# Thermostat_Thorlabs.net
KiCad netlist of a schematic drawn in Altium Designer
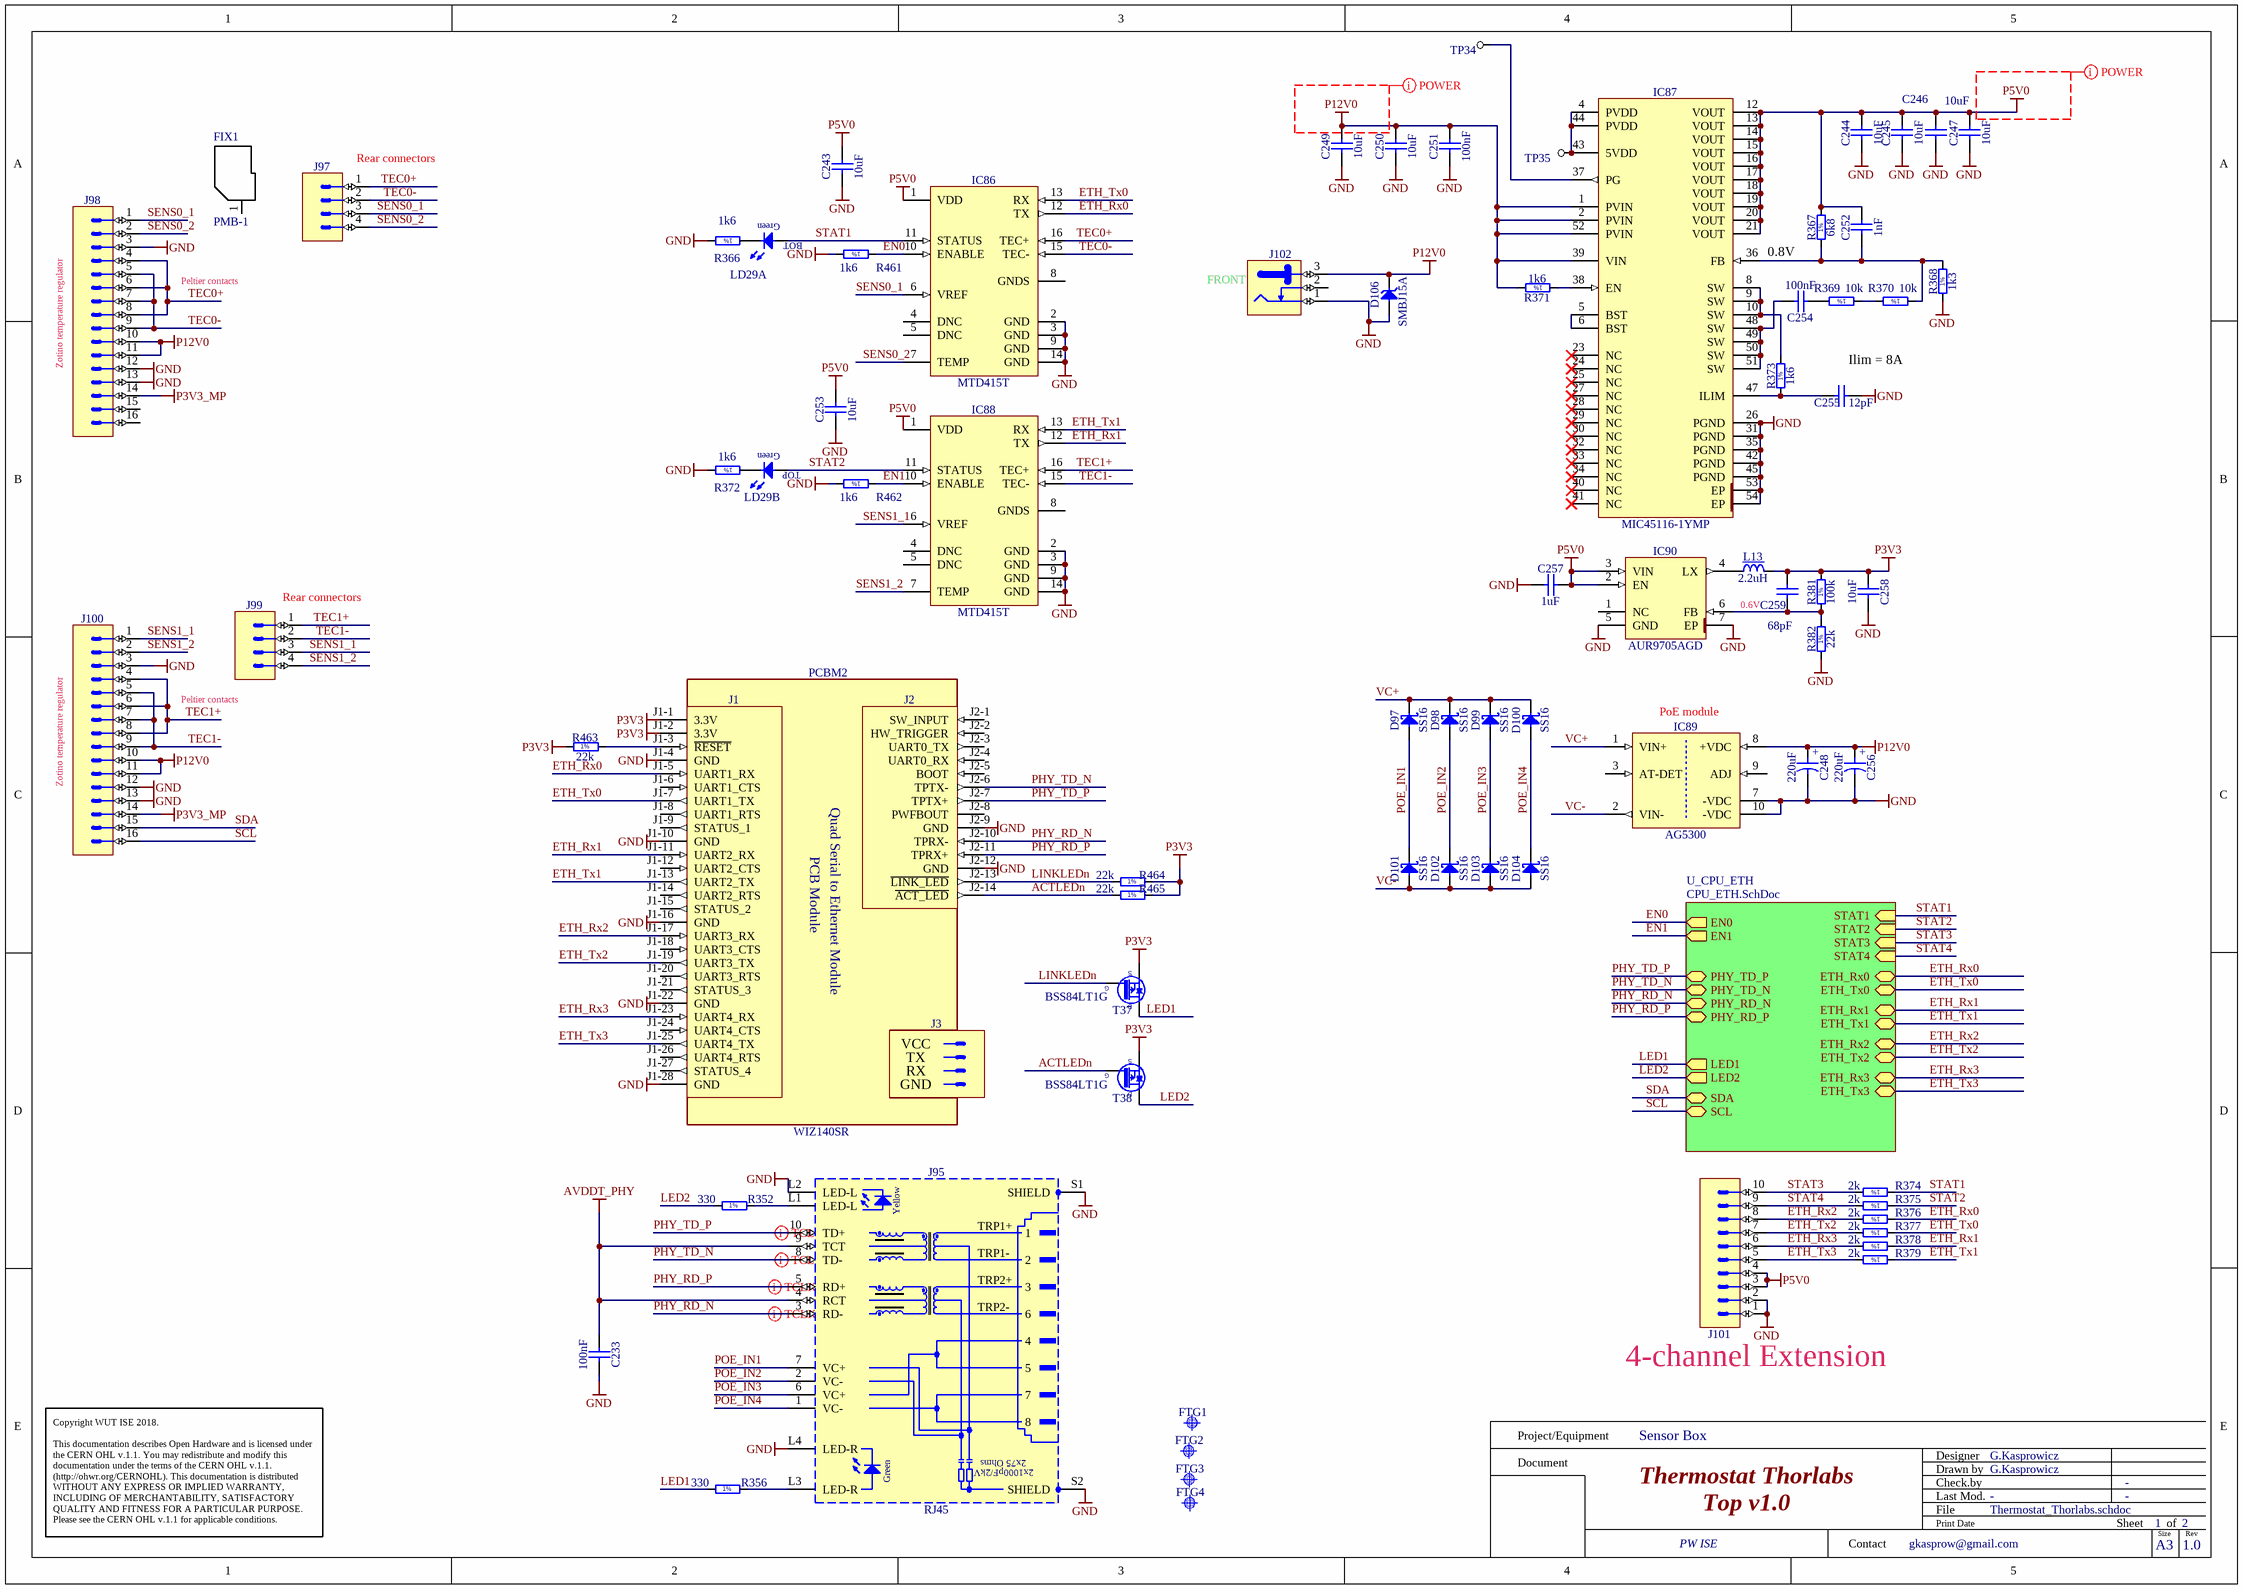
[diagram p0: Thermostat_Thorlabs.schdoc]

(export (version "E")
  (design (tool "Eeschema 10.0.6"))
  (components
    (comp (ref "C233")
      (value "100nF")
      (footprint "CAPC1005X55N")
      (description "Non-polarised capacitor")
      (fields (field (name "PART NUMBER") "CC0402_100NF_16V_10%_X5R") (field (name "VOLTAGE") "16V"))
      (libsource (lib "Capacitors") (part "Capacitor - non polarized"))
    )
    (comp (ref "C243")
      (value "10uF")
      (footprint "CAPC2012X135N")
      (description "Non-polarised capacitor")
      (fields (field (name "PART NUMBER") "CC0805_10UF_16V_10%_X5R") (field (name "VOLTAGE") "16V"))
      (libsource (lib "Capacitors") (part "Capacitor - non polarized"))
    )
    (comp (ref "C244")
      (value "10uF")
      (footprint "CAPC2012X135N")
      (description "Non-polarised capacitor")
      (fields (field (name "PART NUMBER") "CC0805_10UF_16V_10%_X5R") (field (name "VOLTAGE") "16V"))
      (libsource (lib "Capacitors") (part "Capacitor - non polarized"))
    )
    (comp (ref "C245")
      (value "10uF")
      (footprint "CAPC2012X135N")
      (description "Non-polarised capacitor")
      (fields (field (name "PART NUMBER") "CC0805_10UF_16V_10%_X5R") (field (name "VOLTAGE") "16V"))
      (libsource (lib "Capacitors") (part "Capacitor - non polarized"))
    )
    (comp (ref "C246")
      (value "10uF")
      (footprint "CAPC2012X135N")
      (description "Non-polarised capacitor")
      (fields (field (name "PART NUMBER") "CC0805_10UF_16V_10%_X5R") (field (name "VOLTAGE") "16V"))
      (libsource (lib "Capacitors") (part "Capacitor - non polarized"))
    )
    (comp (ref "C247")
      (value "10uF")
      (footprint "CAPC2012X135N")
      (description "Non-polarised capacitor")
      (fields (field (name "PART NUMBER") "CC0805_10UF_16V_10%_X5R") (field (name "VOLTAGE") "16V"))
      (libsource (lib "Capacitors") (part "Capacitor - non polarized"))
    )
    (comp (ref "C248")
      (value "220uF")
      (footprint "CAPMP7343X430N")
      (description "Polarised capacitor")
      (fields (field (name "PART NUMBER") "CTE7343-43_220UF_16V_10%") (field (name "VOLTAGE") "16V"))
      (libsource (lib "Capacitors") (part "Capacitor - polarized"))
    )
    (comp (ref "C249")
      (value "10uF")
      (footprint "CAPC2012X135N")
      (description "Non-polarised capacitor")
      (fields (field (name "PART NUMBER") "CC0805_10UF_16V_10%_X5R") (field (name "VOLTAGE") "16V"))
      (libsource (lib "Capacitors") (part "Capacitor - non polarized"))
    )
    (comp (ref "C250")
      (value "10uF")
      (footprint "CAPC2012X135N")
      (description "Non-polarised capacitor")
      (fields (field (name "PART NUMBER") "CC0805_10UF_16V_10%_X5R") (field (name "VOLTAGE") "16V"))
      (libsource (lib "Capacitors") (part "Capacitor - non polarized"))
    )
    (comp (ref "C251")
      (value "100nF")
      (footprint "CAPC1005X55N")
      (description "Non-polarised capacitor")
      (fields (field (name "PART NUMBER") "CC0402_100NF_16V_10%_X5R") (field (name "VOLTAGE") "16V"))
      (libsource (lib "Capacitors") (part "Capacitor - non polarized"))
    )
    (comp (ref "C252")
      (value "1nF")
      (footprint "CAPC1608X87N")
      (description "Non-polarised capacitor")
      (fields (field (name "PART NUMBER") "CC0603_1NF_100V_10%_X7R") (field (name "VOLTAGE") "100V"))
      (libsource (lib "Capacitors") (part "Capacitor - non polarized"))
    )
    (comp (ref "C253")
      (value "10uF")
      (footprint "CAPC2012X135N")
      (description "Non-polarised capacitor")
      (fields (field (name "PART NUMBER") "CC0805_10UF_16V_10%_X5R") (field (name "VOLTAGE") "16V"))
      (libsource (lib "Capacitors") (part "Capacitor - non polarized"))
    )
    (comp (ref "C254")
      (value "100nF")
      (footprint "CAPC1005X55N")
      (description "Non-polarised capacitor")
      (fields (field (name "PART NUMBER") "CC0402_100NF_16V_10%_X5R") (field (name "VOLTAGE") "16V"))
      (libsource (lib "Capacitors") (part "Capacitor - non polarized"))
    )
    (comp (ref "C255")
      (value "12pF")
      (footprint "CAPC1005X55N")
      (description "Non-polarised capacitor")
      (fields (field (name "PART NUMBER") "CC0402_12PF_50V_5%_C0G") (field (name "VOLTAGE") "50V"))
      (libsource (lib "Capacitors") (part "Capacitor - non polarized"))
    )
    (comp (ref "C256")
      (value "220uF")
      (footprint "CAPMP7343X430N")
      (description "Polarised capacitor")
      (fields (field (name "PART NUMBER") "CTE7343-43_220UF_16V_10%") (field (name "VOLTAGE") "16V"))
      (libsource (lib "Capacitors") (part "Capacitor - polarized"))
    )
    (comp (ref "C257")
      (value "1uF")
      (footprint "CAPC1005X55N")
      (description "Non-polarised capacitor")
      (fields (field (name "PART NUMBER") "CC0402_1UF_16V_10%_X5R") (field (name "VOLTAGE") "16V"))
      (libsource (lib "Capacitors") (part "Capacitor - non polarized"))
    )
    (comp (ref "C258")
      (value "10uF")
      (footprint "CAPC2012X135N")
      (description "Non-polarised capacitor")
      (fields (field (name "PART NUMBER") "CC0805_10UF_16V_10%_X5R") (field (name "VOLTAGE") "16V"))
      (libsource (lib "Capacitors") (part "Capacitor - non polarized"))
    )
    (comp (ref "C259")
      (value "68pF")
      (footprint "CAPC1608X87N")
      (description "Non-polarised capacitor")
      (fields (field (name "PART NUMBER") "CC0603_68PF_50V_5%_NP0") (field (name "VOLTAGE") "50V"))
      (libsource (lib "Capacitors") (part "Capacitor - non polarized"))
    )
    (comp (ref "D97")
      (value "SS16")
      (footprint "DIOM5127X229N")
      (description "Schottky Diode")
      (fields (field (name "VOLTAGE") "60V") (field (name "POWER") "1A"))
      (libsource (lib "ICs And Semiconductors") (part "Diode Schottky"))
    )
    (comp (ref "D98")
      (value "SS16")
      (footprint "DIOM5127X229N")
      (description "Schottky Diode")
      (fields (field (name "VOLTAGE") "60V") (field (name "POWER") "1A"))
      (libsource (lib "ICs And Semiconductors") (part "Diode Schottky"))
    )
    (comp (ref "D99")
      (value "SS16")
      (footprint "DIOM5127X229N")
      (description "Schottky Diode")
      (fields (field (name "VOLTAGE") "60V") (field (name "POWER") "1A"))
      (libsource (lib "ICs And Semiconductors") (part "Diode Schottky"))
    )
    (comp (ref "D100")
      (value "SS16")
      (footprint "DIOM5127X229N")
      (description "Schottky Diode")
      (fields (field (name "VOLTAGE") "60V") (field (name "POWER") "1A"))
      (libsource (lib "ICs And Semiconductors") (part "Diode Schottky"))
    )
    (comp (ref "D101")
      (value "SS16")
      (footprint "DIOM5127X229N")
      (description "Schottky Diode")
      (fields (field (name "VOLTAGE") "60V") (field (name "POWER") "1A"))
      (libsource (lib "ICs And Semiconductors") (part "Diode Schottky"))
    )
    (comp (ref "D102")
      (value "SS16")
      (footprint "DIOM5127X229N")
      (description "Schottky Diode")
      (fields (field (name "VOLTAGE") "60V") (field (name "POWER") "1A"))
      (libsource (lib "ICs And Semiconductors") (part "Diode Schottky"))
    )
    (comp (ref "D103")
      (value "SS16")
      (footprint "DIOM5127X229N")
      (description "Schottky Diode")
      (fields (field (name "VOLTAGE") "60V") (field (name "POWER") "1A"))
      (libsource (lib "ICs And Semiconductors") (part "Diode Schottky"))
    )
    (comp (ref "D104")
      (value "SS16")
      (footprint "DIOM5127X229N")
      (description "Schottky Diode")
      (fields (field (name "VOLTAGE") "60V") (field (name "POWER") "1A"))
      (libsource (lib "ICs And Semiconductors") (part "Diode Schottky"))
    )
    (comp (ref "D106")
      (value "SMBJ15A")
      (footprint "DIOM5336X265N")
      (description "Zener Diode")
      (fields (field (name "VOLTAGE") "15V") (field (name "POWER") "600W"))
      (libsource (lib "ICs And Semiconductors") (part "Diode Zener"))
    )
    (comp (ref "FIX1")
      (value "PMB-1")
      (footprint "PMB-1")
      (description "right angle PCB fixing")
      (libsource (lib "LIBRARY_SCH") (part "MECH_PCB_FIX_RA"))
    )
    (comp (ref "FTG1")
      (value "Use only in PCB")
      (footprint "FIDUCIAL_TOP_C100-200")
      (description "Fiducial Target")
      (fields (field (name "PART NUMBER") "FIDUCIAL_TARGET_C100-200"))
      (libsource (lib "Eletro-mechanical") (part "Fiducial Target"))
    )
    (comp (ref "FTG2")
      (value "Use only in PCB")
      (footprint "FIDUCIAL_TOP_S100-200")
      (description "Fiducial Target")
      (fields (field (name "PART NUMBER") "FIDUCIAL_TARGET_S100-200"))
      (libsource (lib "Eletro-mechanical") (part "Fiducial Target"))
    )
    (comp (ref "FTG3")
      (value "Use only in PCB")
      (footprint "FIDUCIAL_TOP_S200-400")
      (description "Fiducial Target")
      (fields (field (name "PART NUMBER") "FIDUCIAL_TARGET_S200-400"))
      (libsource (lib "Eletro-mechanical") (part "Fiducial Target"))
    )
    (comp (ref "FTG4")
      (value "Use only in PCB")
      (footprint "FIDUCIAL_TOP_S100-200")
      (description "Fiducial Target")
      (fields (field (name "PART NUMBER") "FIDUCIAL_TARGET_S100-200"))
      (libsource (lib "Eletro-mechanical") (part "Fiducial Target"))
    )
    (comp (ref "IC86")
      (value "MTD415T")
      (footprint "THORLABS_MTD415T")
      (description "Miniature Temperature Controller, ±1.5 A, Compatible with 10 kΩ Thermistor")
      (fields (field (name "MANUFACTURER") "THORLABS"))
      (libsource (lib "ICs And Semiconductors") (part "MTD415T"))
    )
    (comp (ref "IC87")
      (value "MIC45116-1YMP")
      (footprint "MICROCHIP_H3QFN88-52LD-PL-3")
      (description "0.8V to 85% PVIN (4.75-19V), 6A Synchronous Step-Down Regulator Module")
      (fields (field (name "MANUFACTURER") "MICROCHIP TECHNOLOGY"))
      (libsource (lib "ICs And Semiconductors") (part "MIC45116"))
    )
    (comp (ref "IC88")
      (value "MTD415T")
      (footprint "THORLABS_MTD415T")
      (description "Miniature Temperature Controller, ±1.5 A, Compatible with 10 kΩ Thermistor")
      (fields (field (name "MANUFACTURER") "THORLABS"))
      (libsource (lib "ICs And Semiconductors") (part "MTD415T"))
    )
    (comp (ref "IC89")
      (value "AG5300")
      (footprint "SILVERTEL_AG5300")
      (description "Power-over-Ethernet Plus (POE+) Module")
      (fields (field (name "MANUFACTURER") "SILVERTEL"))
      (libsource (lib "ICs And Semiconductors") (part "AG5300"))
    )
    (comp (ref "IC90")
      (value "AUR9705AGD")
      (footprint "SON65P200X200X80-7N-R65X145")
      (description "0V to 6V Input, 1A, 1.5MHz, Step-Down DC-DC Converter")
      (fields (field (name "MANUFACTURER") "DIODES INCORPORATED"))
      (libsource (lib "ICs And Semiconductors") (part "AUR9705AGD"))
    )
    (comp (ref "J95")
      (value "RJ45")
      (footprint "ABRACON_ARJM11C7-114-BA-EW2")
      (description "MagJack 10/100BaseT, PoE+, 1X1, OG/Y, -40 to 85*C, Tab Up, RoHS")
      (fields (field (name "PART NUMBER") "ARJM11C7-114-BA-EW2") (field (name "MANUFACTURER") "Abracon"))
      (libsource (lib "LIBRARY_SCH") (part "CON_ETH_POE_ARJM11C7"))
    )
    (comp (ref "J97")
      (value "~")
      (footprint "FCI_20020110-D041A01LF")
      (description "Connector 4 Male")
      (fields (field (name "PART NUMBER") "FCI_20020110-D041A01LF") (field (name "MANUFACTURER") "FCI"))
      (libsource (lib "Connectors") (part "Connector 4 Male"))
    )
    (comp (ref "J98")
      (value "Header 16")
      (footprint "3M_N2516-6002RB")
      (description "Connector 16 Male")
      (fields (field (name "PART NUMBER") "3M_N2516-6002RB") (field (name "MANUFACTURER") "3M"))
      (libsource (lib "Connectors") (part "Connector 16 Male"))
    )
    (comp (ref "J99")
      (value "~")
      (footprint "FCI_20020110-D041A01LF")
      (description "Connector 4 Male")
      (fields (field (name "PART NUMBER") "FCI_20020110-D041A01LF") (field (name "MANUFACTURER") "FCI"))
      (libsource (lib "Connectors") (part "Connector 4 Male"))
    )
    (comp (ref "J100")
      (value "Header 16")
      (footprint "3M_N2516-6002RB")
      (description "Connector 16 Male")
      (fields (field (name "PART NUMBER") "3M_N2516-6002RB") (field (name "MANUFACTURER") "3M"))
      (libsource (lib "Connectors") (part "Connector 16 Male"))
    )
    (comp (ref "J101")
      (value "Header 10")
      (footprint "3M_N2510-6002RB")
      (description "Connector 10 Male")
      (fields (field (name "PART NUMBER") "3M_N2510-6002RB") (field (name "MANUFACTURER") "3M"))
      (libsource (lib "Connectors") (part "Connector 10 Male"))
    )
    (comp (ref "J102")
      (value "Jack")
      (footprint "SWITCHCRAFT_L712RA")
      (description "24V /3. 5A, 2.1mm Diameter Pin, SMD DC Power Supply Connector With  Break Contact")
      (fields (field (name "PART NUMBER") "SWITCHCRAFT_712RA") (field (name "MANUFACTURER") "SWITCHCRAFT"))
      (libsource (lib "LIBRARY_SCH") (part "CON_DC_5A_THT_RA"))
    )
    (comp (ref "L13")
      (value "2.2uH")
      (footprint "IND_MURATA_LQH44PN_P0")
      (description "Inductor With Core")
      (fields
        (field (name "PART NUMBER") "IND_2.2UH_20%_MURATA_LQH44PN2R2MP0L")
        (field (name "POWER") "1.8A")
      )
      (libsource (lib "Inductors & Transformers") (part "Inductor With Magnetic core"))
    )
    (comp (ref "LD29")
      (value "Green/Green")
      (footprint "LED_DIALIGHT_571-0122F")
      (description "LED x2 Green 1C2A-BOT_3C4A-TOP")
      (fields (field (name "PART NUMBER") "LED_DIALIGHT_571-0122F") (field (name "MANUFACTURER") "DIALIGHT"))
      (libsource (lib "ICs And Semiconductors") (part "LED x2 Green 1C2A-BOT_3C4A-TOP"))
    )
    (comp (ref "PCBM2")
      (value "WIZ140SR")
      (footprint "PCBM_WIZNET_WIZ140SR_a")
      (description "Quad Serial to Ethernet Module Based on W5300 & Cortex-M3")
      (fields (field (name "PART NUMBER") "PCBM_WIZNET_WIZ140SR_a") (field (name "MANUFACTURER") "WIZNET"))
      (libsource (lib "ICs And Semiconductors") (part "PCBM_WIZNET_WIZ140SR_a"))
    )
    (comp (ref "R352")
      (value "330")
      (footprint "RESC1005X40N")
      (description "Resistor - 1%")
      (fields (field (name "PART NUMBER") "R0402_330R_1%_0.0625W_100PPM") (field (name "POWER") "0.0625W"))
      (libsource (lib "Resistors") (part "Resistor - 1%"))
    )
    (comp (ref "R356")
      (value "330")
      (footprint "RESC1005X40N")
      (description "Resistor - 1%")
      (fields (field (name "PART NUMBER") "R0402_330R_1%_0.0625W_100PPM") (field (name "POWER") "0.0625W"))
      (libsource (lib "Resistors") (part "Resistor - 1%"))
    )
    (comp (ref "R366")
      (value "1k6")
      (footprint "RESC1005X40N")
      (description "Resistor - 1%")
      (fields (field (name "PART NUMBER") "R0402_1K6_1%_0.0625W_100PPM") (field (name "POWER") "0.0625W"))
      (libsource (lib "Resistors") (part "Resistor - 1%"))
    )
    (comp (ref "R367")
      (value "6k8")
      (footprint "RESC1005X40N")
      (description "Resistor - 1%")
      (fields (field (name "PART NUMBER") "R0402_6K8_1%_0.0625W_100PPM") (field (name "POWER") "0.0625W"))
      (libsource (lib "Resistors") (part "Resistor - 1%"))
    )
    (comp (ref "R368")
      (value "1k3")
      (footprint "RESC1608X55N")
      (description "Resistor - 1%")
      (fields (field (name "PART NUMBER") "R0603_1K3_1%_0.1W_100PPM") (field (name "POWER") "0.1W"))
      (libsource (lib "Resistors") (part "Resistor - 1%"))
    )
    (comp (ref "R369")
      (value "10k")
      (footprint "RESC1005X40N")
      (description "Resistor - 1%")
      (fields (field (name "PART NUMBER") "R0402_10K_1%_0.0625W_100PPM") (field (name "POWER") "0.0625W"))
      (libsource (lib "Resistors") (part "Resistor - 1%"))
    )
    (comp (ref "R370")
      (value "10k")
      (footprint "RESC1005X40N")
      (description "Resistor - 1%")
      (fields (field (name "PART NUMBER") "R0402_10K_1%_0.0625W_100PPM") (field (name "POWER") "0.0625W"))
      (libsource (lib "Resistors") (part "Resistor - 1%"))
    )
    (comp (ref "R371")
      (value "1k6")
      (footprint "RESC1005X40N")
      (description "Resistor - 1%")
      (fields (field (name "PART NUMBER") "R0402_1K6_1%_0.0625W_100PPM") (field (name "POWER") "0.0625W"))
      (libsource (lib "Resistors") (part "Resistor - 1%"))
    )
    (comp (ref "R372")
      (value "1k6")
      (footprint "RESC1005X40N")
      (description "Resistor - 1%")
      (fields (field (name "PART NUMBER") "R0402_1K6_1%_0.0625W_100PPM") (field (name "POWER") "0.0625W"))
      (libsource (lib "Resistors") (part "Resistor - 1%"))
    )
    (comp (ref "R373")
      (value "1k6")
      (footprint "RESC1005X40N")
      (description "Resistor - 1%")
      (fields (field (name "PART NUMBER") "R0402_1K6_1%_0.0625W_100PPM") (field (name "POWER") "0.0625W"))
      (libsource (lib "Resistors") (part "Resistor - 1%"))
    )
    (comp (ref "R374")
      (value "2k")
      (footprint "RESC1005X40N")
      (description "Resistor - 1%")
      (fields (field (name "PART NUMBER") "R0402_2K_1%_0.0625W_100PPM") (field (name "POWER") "0.0625W"))
      (libsource (lib "Resistors") (part "Resistor - 1%"))
    )
    (comp (ref "R375")
      (value "2k")
      (footprint "RESC1005X40N")
      (description "Resistor - 1%")
      (fields (field (name "PART NUMBER") "R0402_2K_1%_0.0625W_100PPM") (field (name "POWER") "0.0625W"))
      (libsource (lib "Resistors") (part "Resistor - 1%"))
    )
    (comp (ref "R376")
      (value "2k")
      (footprint "RESC1005X40N")
      (description "Resistor - 1%")
      (fields (field (name "PART NUMBER") "R0402_2K_1%_0.0625W_100PPM") (field (name "POWER") "0.0625W"))
      (libsource (lib "Resistors") (part "Resistor - 1%"))
    )
    (comp (ref "R377")
      (value "2k")
      (footprint "RESC1005X40N")
      (description "Resistor - 1%")
      (fields (field (name "PART NUMBER") "R0402_2K_1%_0.0625W_100PPM") (field (name "POWER") "0.0625W"))
      (libsource (lib "Resistors") (part "Resistor - 1%"))
    )
    (comp (ref "R378")
      (value "2k")
      (footprint "RESC1005X40N")
      (description "Resistor - 1%")
      (fields (field (name "PART NUMBER") "R0402_2K_1%_0.0625W_100PPM") (field (name "POWER") "0.0625W"))
      (libsource (lib "Resistors") (part "Resistor - 1%"))
    )
    (comp (ref "R379")
      (value "2k")
      (footprint "RESC1005X40N")
      (description "Resistor - 1%")
      (fields (field (name "PART NUMBER") "R0402_2K_1%_0.0625W_100PPM") (field (name "POWER") "0.0625W"))
      (libsource (lib "Resistors") (part "Resistor - 1%"))
    )
    (comp (ref "R381")
      (value "100k")
      (footprint "RESC1005X40N")
      (description "Resistor - 1%")
      (fields (field (name "PART NUMBER") "R0402_100K_1%_0.0625W_100PPM") (field (name "POWER") "0.0625W"))
      (libsource (lib "Resistors") (part "Resistor - 1%"))
    )
    (comp (ref "R382")
      (value "22k")
      (footprint "RESC1005X40N")
      (description "Resistor - 1%")
      (fields (field (name "PART NUMBER") "R0402_22K_1%_0.0625W_100PPM") (field (name "POWER") "0.0625W"))
      (libsource (lib "Resistors") (part "Resistor - 1%"))
    )
    (comp (ref "R461")
      (value "1k6")
      (footprint "RESC1005X40N")
      (description "Resistor - 1%")
      (fields (field (name "PART NUMBER") "R0402_1K6_1%_0.0625W_100PPM") (field (name "POWER") "0.0625W"))
      (libsource (lib "Resistors") (part "Resistor - 1%"))
    )
    (comp (ref "R462")
      (value "1k6")
      (footprint "RESC1005X40N")
      (description "Resistor - 1%")
      (fields (field (name "PART NUMBER") "R0402_1K6_1%_0.0625W_100PPM") (field (name "POWER") "0.0625W"))
      (libsource (lib "Resistors") (part "Resistor - 1%"))
    )
    (comp (ref "R463")
      (value "22k")
      (footprint "RESC1005X40N")
      (description "Resistor - 1%")
      (fields (field (name "PART NUMBER") "R0402_22K_1%_0.0625W_100PPM") (field (name "POWER") "0.0625W"))
      (libsource (lib "Resistors") (part "Resistor - 1%"))
    )
    (comp (ref "R464")
      (value "22k")
      (footprint "RESC1005X40N")
      (description "Resistor - 1%")
      (fields (field (name "PART NUMBER") "R0402_22K_1%_0.0625W_100PPM") (field (name "POWER") "0.0625W"))
      (libsource (lib "Resistors") (part "Resistor - 1%"))
    )
    (comp (ref "R465")
      (value "22k")
      (footprint "RESC1005X40N")
      (description "Resistor - 1%")
      (fields (field (name "PART NUMBER") "R0402_22K_1%_0.0625W_100PPM") (field (name "POWER") "0.0625W"))
      (libsource (lib "Resistors") (part "Resistor - 1%"))
    )
    (comp (ref "T37")
      (value "BSS84LT1G")
      (footprint "SOT95P240X110-3N")
      (description "P-CHANNEL MOSFET WITH DIODE")
      (fields (field (name "MANUFACTURER") "ON SEMICONDUCTOR"))
      (libsource (lib "ICs And Semiconductors") (part "P-MOSFET-D 1G 2S 3D"))
    )
    (comp (ref "T38")
      (value "BSS84LT1G")
      (footprint "SOT95P240X110-3N")
      (description "P-CHANNEL MOSFET WITH DIODE")
      (fields (field (name "MANUFACTURER") "ON SEMICONDUCTOR"))
      (libsource (lib "ICs And Semiconductors") (part "P-MOSFET-D 1G 2S 3D"))
    )
    (comp (ref "TP34")
      (value "TP")
      (footprint "TP")
      (description "Testpoint")
      (libsource (lib "LIBRARY_SCH") (part "TP"))
    )
    (comp (ref "TP35")
      (value "TP")
      (footprint "TP")
      (description "Testpoint")
      (libsource (lib "LIBRARY_SCH") (part "TP"))
    )
  )
  (nets
    (net (code "1") (name "/ACTLEDn") (class "Default")
      (node (ref "PCBM2") (pin "J2-14") (pinfunction "~{ACT_LED}_J2-14") (pintype "output"))
      (node (ref "R465") (pin "1") (pinfunction "1_1") (pintype "passive"))
      (node (ref "T38") (pin "1") (pinfunction "G_1") (pintype "passive"))
    )
    (net (code "2") (name "/EN0") (class "Default")
      (node (ref "IC86") (pin "10") (pinfunction "ENABLE_10") (pintype "input"))
      (node (ref "R461") (pin "1") (pinfunction "1_1") (pintype "passive"))
    )
    (net (code "3") (name "/EN1") (class "Default")
      (node (ref "IC88") (pin "10") (pinfunction "ENABLE_10") (pintype "input"))
      (node (ref "R462") (pin "1") (pinfunction "1_1") (pintype "passive"))
    )
    (net (code "4") (name "/ETH_Rx0") (class "Default")
      (node (ref "IC86") (pin "12") (pinfunction "TX_12") (pintype "output"))
      (node (ref "PCBM2") (pin "J1-5") (pinfunction "UART1_RX_J1-5") (pintype "input"))
      (node (ref "R376") (pin "1") (pinfunction "1_1") (pintype "passive"))
    )
    (net (code "5") (name "/ETH_Rx1") (class "Default")
      (node (ref "IC88") (pin "12") (pinfunction "TX_12") (pintype "output"))
      (node (ref "PCBM2") (pin "J1-11") (pinfunction "UART2_RX_J1-11") (pintype "input"))
      (node (ref "R378") (pin "1") (pinfunction "1_1") (pintype "passive"))
    )
    (net (code "6") (name "/ETH_Rx2") (class "Default")
      (node (ref "J101") (pin "8") (pinfunction "8_8") (pintype "bidirectional"))
      (node (ref "PCBM2") (pin "J1-17") (pinfunction "UART3_RX_J1-17") (pintype "input"))
      (node (ref "R376") (pin "2") (pinfunction "2_2") (pintype "passive"))
    )
    (net (code "7") (name "/ETH_Rx3") (class "Default")
      (node (ref "J101") (pin "6") (pinfunction "6_6") (pintype "bidirectional"))
      (node (ref "PCBM2") (pin "J1-23") (pinfunction "UART4_RX_J1-23") (pintype "input"))
      (node (ref "R378") (pin "2") (pinfunction "2_2") (pintype "passive"))
    )
    (net (code "8") (name "/ETH_Tx0") (class "Default")
      (node (ref "IC86") (pin "13") (pinfunction "RX_13") (pintype "input"))
      (node (ref "PCBM2") (pin "J1-7") (pinfunction "UART1_TX_J1-7") (pintype "output"))
      (node (ref "R377") (pin "1") (pinfunction "1_1") (pintype "passive"))
    )
    (net (code "9") (name "/ETH_Tx1") (class "Default")
      (node (ref "IC88") (pin "13") (pinfunction "RX_13") (pintype "input"))
      (node (ref "PCBM2") (pin "J1-13") (pinfunction "UART2_TX_J1-13") (pintype "output"))
      (node (ref "R379") (pin "1") (pinfunction "1_1") (pintype "passive"))
    )
    (net (code "10") (name "/ETH_Tx2") (class "Default")
      (node (ref "J101") (pin "7") (pinfunction "7_7") (pintype "bidirectional"))
      (node (ref "PCBM2") (pin "J1-19") (pinfunction "UART3_TX_J1-19") (pintype "output"))
      (node (ref "R377") (pin "2") (pinfunction "2_2") (pintype "passive"))
    )
    (net (code "11") (name "/ETH_Tx3") (class "Default")
      (node (ref "J101") (pin "5") (pinfunction "5_5") (pintype "bidirectional"))
      (node (ref "PCBM2") (pin "J1-25") (pinfunction "UART4_TX_J1-25") (pintype "output"))
      (node (ref "R379") (pin "2") (pinfunction "2_2") (pintype "passive"))
    )
    (net (code "12") (name "/LED1") (class "Default")
      (node (ref "R356") (pin "1") (pinfunction "1_1") (pintype "passive"))
      (node (ref "T37") (pin "3") (pinfunction "D_3") (pintype "passive"))
    )
    (net (code "13") (name "/LED2") (class "Default")
      (node (ref "R352") (pin "1") (pinfunction "1_1") (pintype "passive"))
      (node (ref "T38") (pin "3") (pinfunction "D_3") (pintype "passive"))
    )
    (net (code "14") (name "/LINKLEDn") (class "Default")
      (node (ref "PCBM2") (pin "J2-13") (pinfunction "~{LINK_LED}_J2-13") (pintype "output"))
      (node (ref "R464") (pin "1") (pinfunction "1_1") (pintype "passive"))
      (node (ref "T37") (pin "1") (pinfunction "G_1") (pintype "passive"))
    )
    (net (code "15") (name "/PHY_RD_N") (class "Default")
      (node (ref "J95") (pin "3") (pinfunction "RD-_3") (pintype "bidirectional"))
      (node (ref "PCBM2") (pin "J2-10") (pinfunction "TPRX-_J2-10") (pintype "input"))
    )
    (net (code "16") (name "/PHY_RD_P") (class "Default")
      (node (ref "J95") (pin "5") (pinfunction "RD+_5") (pintype "bidirectional"))
      (node (ref "PCBM2") (pin "J2-11") (pinfunction "TPRX+_J2-11") (pintype "input"))
    )
    (net (code "17") (name "/PHY_TD_N") (class "Default")
      (node (ref "J95") (pin "8") (pinfunction "TD-_8") (pintype "bidirectional"))
      (node (ref "PCBM2") (pin "J2-6") (pinfunction "TPTX-_J2-6") (pintype "output"))
    )
    (net (code "18") (name "/PHY_TD_P") (class "Default")
      (node (ref "J95") (pin "10") (pinfunction "TD+_10") (pintype "bidirectional"))
      (node (ref "PCBM2") (pin "J2-7") (pinfunction "TPTX+_J2-7") (pintype "output"))
    )
    (net (code "19") (name "/POE_IN1") (class "Default")
      (node (ref "D101") (pin "1") (pinfunction "C_1") (pintype "passive"))
      (node (ref "D97") (pin "2") (pinfunction "A_2") (pintype "passive"))
      (node (ref "J95") (pin "7") (pinfunction "VC+_7") (pintype "passive"))
    )
    (net (code "20") (name "/POE_IN2") (class "Default")
      (node (ref "D102") (pin "1") (pinfunction "C_1") (pintype "passive"))
      (node (ref "D98") (pin "2") (pinfunction "A_2") (pintype "passive"))
      (node (ref "J95") (pin "2") (pinfunction "VC-_2") (pintype "passive"))
    )
    (net (code "21") (name "/POE_IN3") (class "Default")
      (node (ref "D103") (pin "1") (pinfunction "C_1") (pintype "passive"))
      (node (ref "D99") (pin "2") (pinfunction "A_2") (pintype "passive"))
      (node (ref "J95") (pin "6") (pinfunction "VC+_6") (pintype "passive"))
    )
    (net (code "22") (name "/POE_IN4") (class "Default")
      (node (ref "D100") (pin "2") (pinfunction "A_2") (pintype "passive"))
      (node (ref "D104") (pin "1") (pinfunction "C_1") (pintype "passive"))
      (node (ref "J95") (pin "1") (pinfunction "VC-_1") (pintype "passive"))
    )
    (net (code "23") (name "/SCL") (class "Default")
      (node (ref "J100") (pin "16") (pinfunction "16_16") (pintype "bidirectional"))
    )
    (net (code "24") (name "/SDA") (class "Default")
      (node (ref "J100") (pin "15") (pinfunction "15_15") (pintype "bidirectional"))
    )
    (net (code "25") (name "/SENS0_1") (class "Default")
      (node (ref "IC86") (pin "6") (pinfunction "VREF_6") (pintype "input"))
      (node (ref "J97") (pin "3") (pinfunction "3_3") (pintype "bidirectional"))
      (node (ref "J98") (pin "1") (pinfunction "1_1") (pintype "bidirectional"))
    )
    (net (code "26") (name "/SENS0_2") (class "Default")
      (node (ref "IC86") (pin "7") (pinfunction "TEMP_7") (pintype "passive"))
      (node (ref "J97") (pin "4") (pinfunction "4_4") (pintype "bidirectional"))
      (node (ref "J98") (pin "2") (pinfunction "2_2") (pintype "bidirectional"))
    )
    (net (code "27") (name "/SENS1_1") (class "Default")
      (node (ref "IC88") (pin "6") (pinfunction "VREF_6") (pintype "input"))
      (node (ref "J100") (pin "1") (pinfunction "1_1") (pintype "bidirectional"))
      (node (ref "J99") (pin "3") (pinfunction "3_3") (pintype "bidirectional"))
    )
    (net (code "28") (name "/SENS1_2") (class "Default")
      (node (ref "IC88") (pin "7") (pinfunction "TEMP_7") (pintype "passive"))
      (node (ref "J100") (pin "2") (pinfunction "2_2") (pintype "bidirectional"))
      (node (ref "J99") (pin "4") (pinfunction "4_4") (pintype "bidirectional"))
    )
    (net (code "29") (name "/STAT1") (class "Default")
      (node (ref "IC86") (pin "11") (pinfunction "STATUS_11") (pintype "input"))
      (node (ref "LD29") (pin "2") (pinfunction "A_2") (pintype "passive"))
      (node (ref "R374") (pin "1") (pinfunction "1_1") (pintype "passive"))
    )
    (net (code "30") (name "/STAT2") (class "Default")
      (node (ref "IC88") (pin "11") (pinfunction "STATUS_11") (pintype "input"))
      (node (ref "LD29") (pin "4") (pinfunction "A_4") (pintype "passive"))
      (node (ref "R375") (pin "1") (pinfunction "1_1") (pintype "passive"))
    )
    (net (code "31") (name "/STAT3") (class "Default")
      (node (ref "J101") (pin "10") (pinfunction "10_10") (pintype "bidirectional"))
      (node (ref "R374") (pin "2") (pinfunction "2_2") (pintype "passive"))
    )
    (net (code "32") (name "/STAT4") (class "Default")
      (node (ref "J101") (pin "9") (pinfunction "9_9") (pintype "bidirectional"))
      (node (ref "R375") (pin "2") (pinfunction "2_2") (pintype "passive"))
    )
    (net (code "33") (name "/TEC0+") (class "Default")
      (node (ref "IC86") (pin "16") (pinfunction "TEC+_16") (pintype "input"))
      (node (ref "J97") (pin "1") (pinfunction "1_1") (pintype "bidirectional"))
      (node (ref "J98") (pin "4") (pinfunction "4_4") (pintype "bidirectional"))
      (node (ref "J98") (pin "6") (pinfunction "6_6") (pintype "bidirectional"))
      (node (ref "J98") (pin "8") (pinfunction "8_8") (pintype "bidirectional"))
    )
    (net (code "34") (name "/TEC0-") (class "Default")
      (node (ref "IC86") (pin "15") (pinfunction "TEC-_15") (pintype "input"))
      (node (ref "J97") (pin "2") (pinfunction "2_2") (pintype "bidirectional"))
      (node (ref "J98") (pin "5") (pinfunction "5_5") (pintype "bidirectional"))
      (node (ref "J98") (pin "7") (pinfunction "7_7") (pintype "bidirectional"))
      (node (ref "J98") (pin "9") (pinfunction "9_9") (pintype "bidirectional"))
    )
    (net (code "35") (name "/TEC1+") (class "Default")
      (node (ref "IC88") (pin "16") (pinfunction "TEC+_16") (pintype "input"))
      (node (ref "J100") (pin "4") (pinfunction "4_4") (pintype "bidirectional"))
      (node (ref "J100") (pin "6") (pinfunction "6_6") (pintype "bidirectional"))
      (node (ref "J100") (pin "8") (pinfunction "8_8") (pintype "bidirectional"))
      (node (ref "J99") (pin "1") (pinfunction "1_1") (pintype "bidirectional"))
    )
    (net (code "36") (name "/TEC1-") (class "Default")
      (node (ref "IC88") (pin "15") (pinfunction "TEC-_15") (pintype "input"))
      (node (ref "J100") (pin "5") (pinfunction "5_5") (pintype "bidirectional"))
      (node (ref "J100") (pin "7") (pinfunction "7_7") (pintype "bidirectional"))
      (node (ref "J100") (pin "9") (pinfunction "9_9") (pintype "bidirectional"))
      (node (ref "J99") (pin "2") (pinfunction "2_2") (pintype "bidirectional"))
    )
    (net (code "37") (name "/VC+") (class "Default")
      (node (ref "D100") (pin "1") (pinfunction "C_1") (pintype "passive"))
      (node (ref "D97") (pin "1") (pinfunction "C_1") (pintype "passive"))
      (node (ref "D98") (pin "1") (pinfunction "C_1") (pintype "passive"))
      (node (ref "D99") (pin "1") (pinfunction "C_1") (pintype "passive"))
      (node (ref "IC89") (pin "1") (pinfunction "VIN+_1") (pintype "input"))
    )
    (net (code "38") (name "/VC-") (class "Default")
      (node (ref "D101") (pin "2") (pinfunction "A_2") (pintype "passive"))
      (node (ref "D102") (pin "2") (pinfunction "A_2") (pintype "passive"))
      (node (ref "D103") (pin "2") (pinfunction "A_2") (pintype "passive"))
      (node (ref "D104") (pin "2") (pinfunction "A_2") (pintype "passive"))
      (node (ref "IC89") (pin "2") (pinfunction "VIN-_2") (pintype "output"))
    )
    (net (code "39") (name "AVDDT_PHY") (class "Default")
      (node (ref "C233") (pin "2") (pinfunction "2_2") (pintype "passive"))
      (node (ref "J95") (pin "4") (pinfunction "RCT_4") (pintype "bidirectional"))
      (node (ref "J95") (pin "9") (pinfunction "TCT_9") (pintype "bidirectional"))
    )
    (net (code "40") (name "GND") (class "Default")
      (node (ref "C233") (pin "1") (pinfunction "1_1") (pintype "passive"))
      (node (ref "C243") (pin "1") (pinfunction "1_1") (pintype "passive"))
      (node (ref "C244") (pin "1") (pinfunction "1_1") (pintype "passive"))
      (node (ref "C245") (pin "1") (pinfunction "1_1") (pintype "passive"))
      (node (ref "C246") (pin "1") (pinfunction "1_1") (pintype "passive"))
      (node (ref "C247") (pin "1") (pinfunction "1_1") (pintype "passive"))
      (node (ref "C248") (pin "2") (pinfunction "2_2") (pintype "passive"))
      (node (ref "C249") (pin "1") (pinfunction "1_1") (pintype "passive"))
      (node (ref "C250") (pin "1") (pinfunction "1_1") (pintype "passive"))
      (node (ref "C251") (pin "1") (pinfunction "1_1") (pintype "passive"))
      (node (ref "C253") (pin "1") (pinfunction "1_1") (pintype "passive"))
      (node (ref "C255") (pin "1") (pinfunction "1_1") (pintype "passive"))
      (node (ref "C256") (pin "2") (pinfunction "2_2") (pintype "passive"))
      (node (ref "C257") (pin "1") (pinfunction "1_1") (pintype "passive"))
      (node (ref "C258") (pin "2") (pinfunction "2_2") (pintype "passive"))
      (node (ref "D106") (pin "2") (pinfunction "A_2") (pintype "passive"))
      (node (ref "IC86") (pin "14") (pinfunction "GND_14") (pintype "power_in"))
      (node (ref "IC86") (pin "2") (pinfunction "GND_2") (pintype "power_in"))
      (node (ref "IC86") (pin "3") (pinfunction "GND_3") (pintype "power_in"))
      (node (ref "IC86") (pin "9") (pinfunction "GND_9") (pintype "power_in"))
      (node (ref "IC87") (pin "26") (pinfunction "PGND_26") (pintype "power_in"))
      (node (ref "IC87") (pin "31") (pinfunction "PGND_31") (pintype "power_in"))
      (node (ref "IC87") (pin "35") (pinfunction "PGND_35") (pintype "power_in"))
      (node (ref "IC87") (pin "42") (pinfunction "PGND_42") (pintype "power_in"))
      (node (ref "IC87") (pin "45") (pinfunction "PGND_45") (pintype "power_in"))
      (node (ref "IC87") (pin "53") (pinfunction "EP_53") (pintype "power_in"))
      (node (ref "IC87") (pin "54") (pinfunction "EP_54") (pintype "power_in"))
      (node (ref "IC88") (pin "14") (pinfunction "GND_14") (pintype "power_in"))
      (node (ref "IC88") (pin "2") (pinfunction "GND_2") (pintype "power_in"))
      (node (ref "IC88") (pin "3") (pinfunction "GND_3") (pintype "power_in"))
      (node (ref "IC88") (pin "9") (pinfunction "GND_9") (pintype "power_in"))
      (node (ref "IC89") (pin "10") (pinfunction "-VDC_10") (pintype "power_in"))
      (node (ref "IC89") (pin "7") (pinfunction "-VDC_7") (pintype "power_in"))
      (node (ref "IC90") (pin "5") (pinfunction "GND_5") (pintype "power_in"))
      (node (ref "IC90") (pin "7") (pinfunction "EP_7") (pintype "passive"))
      (node (ref "J100") (pin "12") (pinfunction "12_12") (pintype "bidirectional"))
      (node (ref "J100") (pin "13") (pinfunction "13_13") (pintype "bidirectional"))
      (node (ref "J100") (pin "3") (pinfunction "3_3") (pintype "bidirectional"))
      (node (ref "J101") (pin "1") (pinfunction "1_1") (pintype "bidirectional"))
      (node (ref "J101") (pin "2") (pinfunction "2_2") (pintype "bidirectional"))
      (node (ref "J102") (pin "1") (pinfunction "1_1") (pintype "bidirectional"))
      (node (ref "J95") (pin "L2") (pinfunction "LED-L_L2") (pintype "passive"))
      (node (ref "J95") (pin "L4") (pinfunction "LED-R_L4") (pintype "passive"))
      (node (ref "J95") (pin "S1") (pinfunction "SHIELD_S1") (pintype "power_in"))
      (node (ref "J95") (pin "S2") (pinfunction "SHIELD_S2") (pintype "power_in"))
      (node (ref "J98") (pin "12") (pinfunction "12_12") (pintype "bidirectional"))
      (node (ref "J98") (pin "13") (pinfunction "13_13") (pintype "bidirectional"))
      (node (ref "J98") (pin "3") (pinfunction "3_3") (pintype "bidirectional"))
      (node (ref "PCBM2") (pin "J1-10") (pinfunction "GND_J1-10") (pintype "power_in"))
      (node (ref "PCBM2") (pin "J1-16") (pinfunction "GND_J1-16") (pintype "power_in"))
      (node (ref "PCBM2") (pin "J1-22") (pinfunction "GND_J1-22") (pintype "power_in"))
      (node (ref "PCBM2") (pin "J1-28") (pinfunction "GND_J1-28") (pintype "power_in"))
      (node (ref "PCBM2") (pin "J1-4") (pinfunction "GND_J1-4") (pintype "power_in"))
      (node (ref "PCBM2") (pin "J2-12") (pinfunction "GND_J2-12") (pintype "power_in"))
      (node (ref "PCBM2") (pin "J2-9") (pinfunction "GND_J2-9") (pintype "power_in"))
      (node (ref "R366") (pin "2") (pinfunction "2_2") (pintype "passive"))
      (node (ref "R368") (pin "1") (pinfunction "1_1") (pintype "passive"))
      (node (ref "R372") (pin "2") (pinfunction "2_2") (pintype "passive"))
      (node (ref "R382") (pin "1") (pinfunction "1_1") (pintype "passive"))
      (node (ref "R461") (pin "2") (pinfunction "2_2") (pintype "passive"))
      (node (ref "R462") (pin "2") (pinfunction "2_2") (pintype "passive"))
    )
    (net (code "41") (name "Net-(C254-Pad1)") (class "Default")
      (node (ref "C254") (pin "1") (pinfunction "1_1") (pintype "passive"))
      (node (ref "R369") (pin "2") (pinfunction "2_2") (pintype "passive"))
    )
    (net (code "42") (name "Net-(C254-Pad2)") (class "Default")
      (node (ref "C254") (pin "2") (pinfunction "2_2") (pintype "passive"))
      (node (ref "IC87") (pin "48") (pinfunction "SW_48") (pintype "passive"))
      (node (ref "IC87") (pin "49") (pinfunction "SW_49") (pintype "passive"))
      (node (ref "IC87") (pin "50") (pinfunction "SW_50") (pintype "passive"))
      (node (ref "IC87") (pin "51") (pinfunction "SW_51") (pintype "passive"))
    )
    (net (code "43") (name "Net-(IC87-5VDD)") (class "Default")
      (node (ref "IC87") (pin "4") (pinfunction "PVDD_4") (pintype "power_in"))
      (node (ref "IC87") (pin "43") (pinfunction "5VDD_43") (pintype "power_in"))
      (node (ref "IC87") (pin "44") (pinfunction "PVDD_44") (pintype "power_in"))
      (node (ref "TP35") (pin "1") (pintype "passive"))
    )
    (net (code "44") (name "Net-(IC87-BST-Pad5)") (class "Default")
      (node (ref "IC87") (pin "5") (pinfunction "BST_5") (pintype "passive"))
      (node (ref "IC87") (pin "6") (pinfunction "BST_6") (pintype "passive"))
    )
    (net (code "45") (name "Net-(IC87-EN)") (class "Default")
      (node (ref "IC87") (pin "38") (pinfunction "EN_38") (pintype "input"))
      (node (ref "R371") (pin "1") (pinfunction "1_1") (pintype "passive"))
    )
    (net (code "46") (name "Net-(IC87-FB)") (class "Default")
      (node (ref "C252") (pin "1") (pinfunction "1_1") (pintype "passive"))
      (node (ref "IC87") (pin "36") (pinfunction "FB_36") (pintype "input"))
      (node (ref "R367") (pin "1") (pinfunction "1_1") (pintype "passive"))
      (node (ref "R368") (pin "2") (pinfunction "2_2") (pintype "passive"))
      (node (ref "R370") (pin "1") (pinfunction "1_1") (pintype "passive"))
    )
    (net (code "47") (name "Net-(IC87-ILIM)") (class "Default")
      (node (ref "C255") (pin "2") (pinfunction "2_2") (pintype "passive"))
      (node (ref "IC87") (pin "47") (pinfunction "ILIM_47") (pintype "passive"))
      (node (ref "R373") (pin "1") (pinfunction "1_1") (pintype "passive"))
    )
    (net (code "48") (name "Net-(IC87-PG)") (class "Default")
      (node (ref "IC87") (pin "37") (pinfunction "PG_37") (pintype "output"))
      (node (ref "TP34") (pin "1") (pintype "passive"))
    )
    (net (code "49") (name "Net-(IC87-SW-Pad10)") (class "Default")
      (node (ref "IC87") (pin "10") (pinfunction "SW_10") (pintype "passive"))
      (node (ref "IC87") (pin "8") (pinfunction "SW_8") (pintype "passive"))
      (node (ref "IC87") (pin "9") (pinfunction "SW_9") (pintype "passive"))
      (node (ref "R373") (pin "2") (pinfunction "2_2") (pintype "passive"))
    )
    (net (code "50") (name "Net-(IC90-FB)") (class "Default")
      (node (ref "C259") (pin "1") (pinfunction "1_1") (pintype "passive"))
      (node (ref "IC90") (pin "6") (pinfunction "FB_6") (pintype "input"))
      (node (ref "R381") (pin "1") (pinfunction "1_1") (pintype "passive"))
      (node (ref "R382") (pin "2") (pinfunction "2_2") (pintype "passive"))
    )
    (net (code "51") (name "Net-(IC90-LX)") (class "Default")
      (node (ref "IC90") (pin "4") (pinfunction "LX_4") (pintype "output"))
      (node (ref "L13") (pin "1") (pinfunction "1_1") (pintype "passive"))
    )
    (net (code "52") (name "Net-(J95-LED-L-PadL1)") (class "Default")
      (node (ref "J95") (pin "L1") (pinfunction "LED-L_L1") (pintype "passive"))
      (node (ref "R352") (pin "2") (pinfunction "2_2") (pintype "passive"))
    )
    (net (code "53") (name "Net-(J95-LED-R-PadL3)") (class "Default")
      (node (ref "J95") (pin "L3") (pinfunction "LED-R_L3") (pintype "passive"))
      (node (ref "R356") (pin "2") (pinfunction "2_2") (pintype "passive"))
    )
    (net (code "54") (name "Net-(LD29A-C)") (class "Default")
      (node (ref "LD29") (pin "1") (pinfunction "C_1") (pintype "passive"))
      (node (ref "R366") (pin "1") (pinfunction "1_1") (pintype "passive"))
    )
    (net (code "55") (name "Net-(LD29B-C)") (class "Default")
      (node (ref "LD29") (pin "3") (pinfunction "C_3") (pintype "passive"))
      (node (ref "R372") (pin "1") (pinfunction "1_1") (pintype "passive"))
    )
    (net (code "56") (name "Net-(PCBM2-~{RESET})") (class "Default")
      (node (ref "PCBM2") (pin "J1-3") (pinfunction "~{RESET}_J1-3") (pintype "input"))
      (node (ref "R463") (pin "2") (pinfunction "2_2") (pintype "passive"))
    )
    (net (code "57") (name "Net-(R369-Pad1)") (class "Default")
      (node (ref "R369") (pin "1") (pinfunction "1_1") (pintype "passive"))
      (node (ref "R370") (pin "2") (pinfunction "2_2") (pintype "passive"))
    )
    (net (code "58") (name "P3V3") (class "Default")
      (node (ref "C258") (pin "1") (pinfunction "1_1") (pintype "passive"))
      (node (ref "C259") (pin "2") (pinfunction "2_2") (pintype "passive"))
      (node (ref "L13") (pin "2") (pinfunction "2_2") (pintype "passive"))
      (node (ref "PCBM2") (pin "J1-1") (pinfunction "3.3V_J1-1") (pintype "power_in"))
      (node (ref "PCBM2") (pin "J1-2") (pinfunction "3.3V_J1-2") (pintype "power_in"))
      (node (ref "R381") (pin "2") (pinfunction "2_2") (pintype "passive"))
      (node (ref "R463") (pin "1") (pinfunction "1_1") (pintype "passive"))
      (node (ref "R464") (pin "2") (pinfunction "2_2") (pintype "passive"))
      (node (ref "R465") (pin "2") (pinfunction "2_2") (pintype "passive"))
      (node (ref "T37") (pin "2") (pinfunction "S_2") (pintype "passive"))
      (node (ref "T38") (pin "2") (pinfunction "S_2") (pintype "passive"))
    )
    (net (code "59") (name "P3V3_MP") (class "Default")
      (node (ref "J100") (pin "14") (pinfunction "14_14") (pintype "bidirectional"))
      (node (ref "J98") (pin "14") (pinfunction "14_14") (pintype "bidirectional"))
    )
    (net (code "60") (name "P5V0") (class "Default")
      (node (ref "C243") (pin "2") (pinfunction "2_2") (pintype "passive"))
      (node (ref "C244") (pin "2") (pinfunction "2_2") (pintype "passive"))
      (node (ref "C245") (pin "2") (pinfunction "2_2") (pintype "passive"))
      (node (ref "C246") (pin "2") (pinfunction "2_2") (pintype "passive"))
      (node (ref "C247") (pin "2") (pinfunction "2_2") (pintype "passive"))
      (node (ref "C252") (pin "2") (pinfunction "2_2") (pintype "passive"))
      (node (ref "C253") (pin "2") (pinfunction "2_2") (pintype "passive"))
      (node (ref "C257") (pin "2") (pinfunction "2_2") (pintype "passive"))
      (node (ref "IC86") (pin "1") (pinfunction "VDD_1") (pintype "power_in"))
      (node (ref "IC87") (pin "12") (pinfunction "VOUT_12") (pintype "power_in"))
      (node (ref "IC87") (pin "13") (pinfunction "VOUT_13") (pintype "power_in"))
      (node (ref "IC87") (pin "14") (pinfunction "VOUT_14") (pintype "power_in"))
      (node (ref "IC87") (pin "15") (pinfunction "VOUT_15") (pintype "power_in"))
      (node (ref "IC87") (pin "16") (pinfunction "VOUT_16") (pintype "power_in"))
      (node (ref "IC87") (pin "17") (pinfunction "VOUT_17") (pintype "power_in"))
      (node (ref "IC87") (pin "18") (pinfunction "VOUT_18") (pintype "power_in"))
      (node (ref "IC87") (pin "19") (pinfunction "VOUT_19") (pintype "power_in"))
      (node (ref "IC87") (pin "20") (pinfunction "VOUT_20") (pintype "power_in"))
      (node (ref "IC87") (pin "21") (pinfunction "VOUT_21") (pintype "power_in"))
      (node (ref "IC88") (pin "1") (pinfunction "VDD_1") (pintype "power_in"))
      (node (ref "IC90") (pin "2") (pinfunction "EN_2") (pintype "input"))
      (node (ref "IC90") (pin "3") (pinfunction "VIN_3") (pintype "input"))
      (node (ref "J101") (pin "3") (pinfunction "3_3") (pintype "bidirectional"))
      (node (ref "J101") (pin "4") (pinfunction "4_4") (pintype "bidirectional"))
      (node (ref "R367") (pin "2") (pinfunction "2_2") (pintype "passive"))
    )
    (net (code "61") (name "P12V0") (class "Default")
      (node (ref "C248") (pin "1") (pinfunction "1_1") (pintype "passive"))
      (node (ref "C249") (pin "2") (pinfunction "2_2") (pintype "passive"))
      (node (ref "C250") (pin "2") (pinfunction "2_2") (pintype "passive"))
      (node (ref "C251") (pin "2") (pinfunction "2_2") (pintype "passive"))
      (node (ref "C256") (pin "1") (pinfunction "1_1") (pintype "passive"))
      (node (ref "D106") (pin "1") (pinfunction "C_1") (pintype "passive"))
      (node (ref "IC87") (pin "1") (pinfunction "PVIN_1") (pintype "power_in"))
      (node (ref "IC87") (pin "2") (pinfunction "PVIN_2") (pintype "power_in"))
      (node (ref "IC87") (pin "39") (pinfunction "VIN_39") (pintype "power_in"))
      (node (ref "IC87") (pin "52") (pinfunction "PVIN_52") (pintype "power_in"))
      (node (ref "IC89") (pin "8") (pinfunction "+VDC_8") (pintype "input"))
      (node (ref "J100") (pin "10") (pinfunction "10_10") (pintype "bidirectional"))
      (node (ref "J100") (pin "11") (pinfunction "11_11") (pintype "bidirectional"))
      (node (ref "J102") (pin "3") (pinfunction "3_3") (pintype "bidirectional"))
      (node (ref "J98") (pin "10") (pinfunction "10_10") (pintype "bidirectional"))
      (node (ref "J98") (pin "11") (pinfunction "11_11") (pintype "bidirectional"))
      (node (ref "R371") (pin "2") (pinfunction "2_2") (pintype "passive"))
    )
    (net (code "62") (name "unconnected-(FIX1-Pad1)") (class "Default")
      (node (ref "FIX1") (pin "1") (pinfunction "1_1") (pintype "passive"))
    )
    (net (code "63") (name "unconnected-(IC86-DNC-Pad4)") (class "Default")
      (node (ref "IC86") (pin "4") (pinfunction "DNC_4") (pintype "passive"))
    )
    (net (code "64") (name "unconnected-(IC86-DNC-Pad5)") (class "Default")
      (node (ref "IC86") (pin "5") (pinfunction "DNC_5") (pintype "passive"))
    )
    (net (code "65") (name "unconnected-(IC86-GNDS-Pad8)") (class "Default")
      (node (ref "IC86") (pin "8") (pinfunction "GNDS_8") (pintype "power_in"))
    )
    (net (code "66") (name "unconnected-(IC87-NC-Pad23)") (class "Default")
      (node (ref "IC87") (pin "23") (pinfunction "NC_23") (pintype "passive+no_connect"))
    )
    (net (code "67") (name "unconnected-(IC87-NC-Pad24)") (class "Default")
      (node (ref "IC87") (pin "24") (pinfunction "NC_24") (pintype "passive+no_connect"))
    )
    (net (code "68") (name "unconnected-(IC87-NC-Pad25)") (class "Default")
      (node (ref "IC87") (pin "25") (pinfunction "NC_25") (pintype "passive+no_connect"))
    )
    (net (code "69") (name "unconnected-(IC87-NC-Pad27)") (class "Default")
      (node (ref "IC87") (pin "27") (pinfunction "NC_27") (pintype "passive+no_connect"))
    )
    (net (code "70") (name "unconnected-(IC87-NC-Pad28)") (class "Default")
      (node (ref "IC87") (pin "28") (pinfunction "NC_28") (pintype "passive+no_connect"))
    )
    (net (code "71") (name "unconnected-(IC87-NC-Pad29)") (class "Default")
      (node (ref "IC87") (pin "29") (pinfunction "NC_29") (pintype "passive+no_connect"))
    )
    (net (code "72") (name "unconnected-(IC87-NC-Pad30)") (class "Default")
      (node (ref "IC87") (pin "30") (pinfunction "NC_30") (pintype "passive+no_connect"))
    )
    (net (code "73") (name "unconnected-(IC87-NC-Pad32)") (class "Default")
      (node (ref "IC87") (pin "32") (pinfunction "NC_32") (pintype "passive+no_connect"))
    )
    (net (code "74") (name "unconnected-(IC87-NC-Pad33)") (class "Default")
      (node (ref "IC87") (pin "33") (pinfunction "NC_33") (pintype "passive+no_connect"))
    )
    (net (code "75") (name "unconnected-(IC87-NC-Pad34)") (class "Default")
      (node (ref "IC87") (pin "34") (pinfunction "NC_34") (pintype "passive+no_connect"))
    )
    (net (code "76") (name "unconnected-(IC87-NC-Pad40)") (class "Default")
      (node (ref "IC87") (pin "40") (pinfunction "NC_40") (pintype "passive+no_connect"))
    )
    (net (code "77") (name "unconnected-(IC87-NC-Pad41)") (class "Default")
      (node (ref "IC87") (pin "41") (pinfunction "NC_41") (pintype "passive+no_connect"))
    )
    (net (code "78") (name "unconnected-(IC88-DNC-Pad4)") (class "Default")
      (node (ref "IC88") (pin "4") (pinfunction "DNC_4") (pintype "passive"))
    )
    (net (code "79") (name "unconnected-(IC88-DNC-Pad5)") (class "Default")
      (node (ref "IC88") (pin "5") (pinfunction "DNC_5") (pintype "passive"))
    )
    (net (code "80") (name "unconnected-(IC88-GNDS-Pad8)") (class "Default")
      (node (ref "IC88") (pin "8") (pinfunction "GNDS_8") (pintype "power_in"))
    )
    (net (code "81") (name "unconnected-(IC89-ADJ-Pad9)") (class "Default")
      (node (ref "IC89") (pin "9") (pinfunction "ADJ_9") (pintype "input"))
    )
    (net (code "82") (name "unconnected-(IC89-AT-DET-Pad3)") (class "Default")
      (node (ref "IC89") (pin "3") (pinfunction "AT-DET_3") (pintype "input"))
    )
    (net (code "83") (name "unconnected-(IC90-NC-Pad1)") (class "Default")
      (node (ref "IC90") (pin "1") (pinfunction "NC_1") (pintype "passive"))
    )
    (net (code "84") (name "unconnected-(J98-Pad15)") (class "Default")
      (node (ref "J98") (pin "15") (pinfunction "15_15") (pintype "bidirectional"))
    )
    (net (code "85") (name "unconnected-(J98-Pad16)") (class "Default")
      (node (ref "J98") (pin "16") (pinfunction "16_16") (pintype "bidirectional"))
    )
    (net (code "86") (name "unconnected-(J102-Pad2)") (class "Default")
      (node (ref "J102") (pin "2") (pinfunction "2_2") (pintype "bidirectional"))
    )
    (net (code "87") (name "unconnected-(PCBM2-BOOT-PadJ2-5)") (class "Default")
      (node (ref "PCBM2") (pin "J2-5") (pinfunction "BOOT_J2-5") (pintype "input"))
    )
    (net (code "88") (name "unconnected-(PCBM2-HW_TRIGGER-PadJ2-2)") (class "Default")
      (node (ref "PCBM2") (pin "J2-2") (pinfunction "HW_TRIGGER_J2-2") (pintype "input"))
    )
    (net (code "89") (name "unconnected-(PCBM2-PWFBOUT-PadJ2-8)") (class "Default")
      (node (ref "PCBM2") (pin "J2-8") (pinfunction "PWFBOUT_J2-8") (pintype "power_in"))
    )
    (net (code "90") (name "unconnected-(PCBM2-STATUS_1-PadJ1-9)") (class "Default")
      (node (ref "PCBM2") (pin "J1-9") (pinfunction "STATUS_1_J1-9") (pintype "output"))
    )
    (net (code "91") (name "unconnected-(PCBM2-STATUS_2-PadJ1-15)") (class "Default")
      (node (ref "PCBM2") (pin "J1-15") (pinfunction "STATUS_2_J1-15") (pintype "output"))
    )
    (net (code "92") (name "unconnected-(PCBM2-STATUS_3-PadJ1-21)") (class "Default")
      (node (ref "PCBM2") (pin "J1-21") (pinfunction "STATUS_3_J1-21") (pintype "output"))
    )
    (net (code "93") (name "unconnected-(PCBM2-STATUS_4-PadJ1-27)") (class "Default")
      (node (ref "PCBM2") (pin "J1-27") (pinfunction "STATUS_4_J1-27") (pintype "output"))
    )
    (net (code "94") (name "unconnected-(PCBM2-SW_INPUT-PadJ2-1)") (class "Default")
      (node (ref "PCBM2") (pin "J2-1") (pinfunction "SW_INPUT_J2-1") (pintype "input"))
    )
    (net (code "95") (name "unconnected-(PCBM2-UART0_RX-PadJ2-4)") (class "Default")
      (node (ref "PCBM2") (pin "J2-4") (pinfunction "UART0_RX_J2-4") (pintype "input"))
    )
    (net (code "96") (name "unconnected-(PCBM2-UART0_TX-PadJ2-3)") (class "Default")
      (node (ref "PCBM2") (pin "J2-3") (pinfunction "UART0_TX_J2-3") (pintype "output"))
    )
    (net (code "97") (name "unconnected-(PCBM2-UART1_CTS-PadJ1-6)") (class "Default")
      (node (ref "PCBM2") (pin "J1-6") (pinfunction "UART1_CTS_J1-6") (pintype "input"))
    )
    (net (code "98") (name "unconnected-(PCBM2-UART1_RTS-PadJ1-8)") (class "Default")
      (node (ref "PCBM2") (pin "J1-8") (pinfunction "UART1_RTS_J1-8") (pintype "output"))
    )
    (net (code "99") (name "unconnected-(PCBM2-UART2_CTS-PadJ1-12)") (class "Default")
      (node (ref "PCBM2") (pin "J1-12") (pinfunction "UART2_CTS_J1-12") (pintype "input"))
    )
    (net (code "100") (name "unconnected-(PCBM2-UART2_RTS-PadJ1-14)") (class "Default")
      (node (ref "PCBM2") (pin "J1-14") (pinfunction "UART2_RTS_J1-14") (pintype "output"))
    )
    (net (code "101") (name "unconnected-(PCBM2-UART3_CTS-PadJ1-18)") (class "Default")
      (node (ref "PCBM2") (pin "J1-18") (pinfunction "UART3_CTS_J1-18") (pintype "input"))
    )
    (net (code "102") (name "unconnected-(PCBM2-UART3_RTS-PadJ1-20)") (class "Default")
      (node (ref "PCBM2") (pin "J1-20") (pinfunction "UART3_RTS_J1-20") (pintype "output"))
    )
    (net (code "103") (name "unconnected-(PCBM2-UART4_CTS-PadJ1-24)") (class "Default")
      (node (ref "PCBM2") (pin "J1-24") (pinfunction "UART4_CTS_J1-24") (pintype "input"))
    )
    (net (code "104") (name "unconnected-(PCBM2-UART4_RTS-PadJ1-26)") (class "Default")
      (node (ref "PCBM2") (pin "J1-26") (pinfunction "UART4_RTS_J1-26") (pintype "output"))
    )
  )
)
